# opensourus_voltceraptor_v1.net
KiCad netlist of a schematic drawn in EAGLE
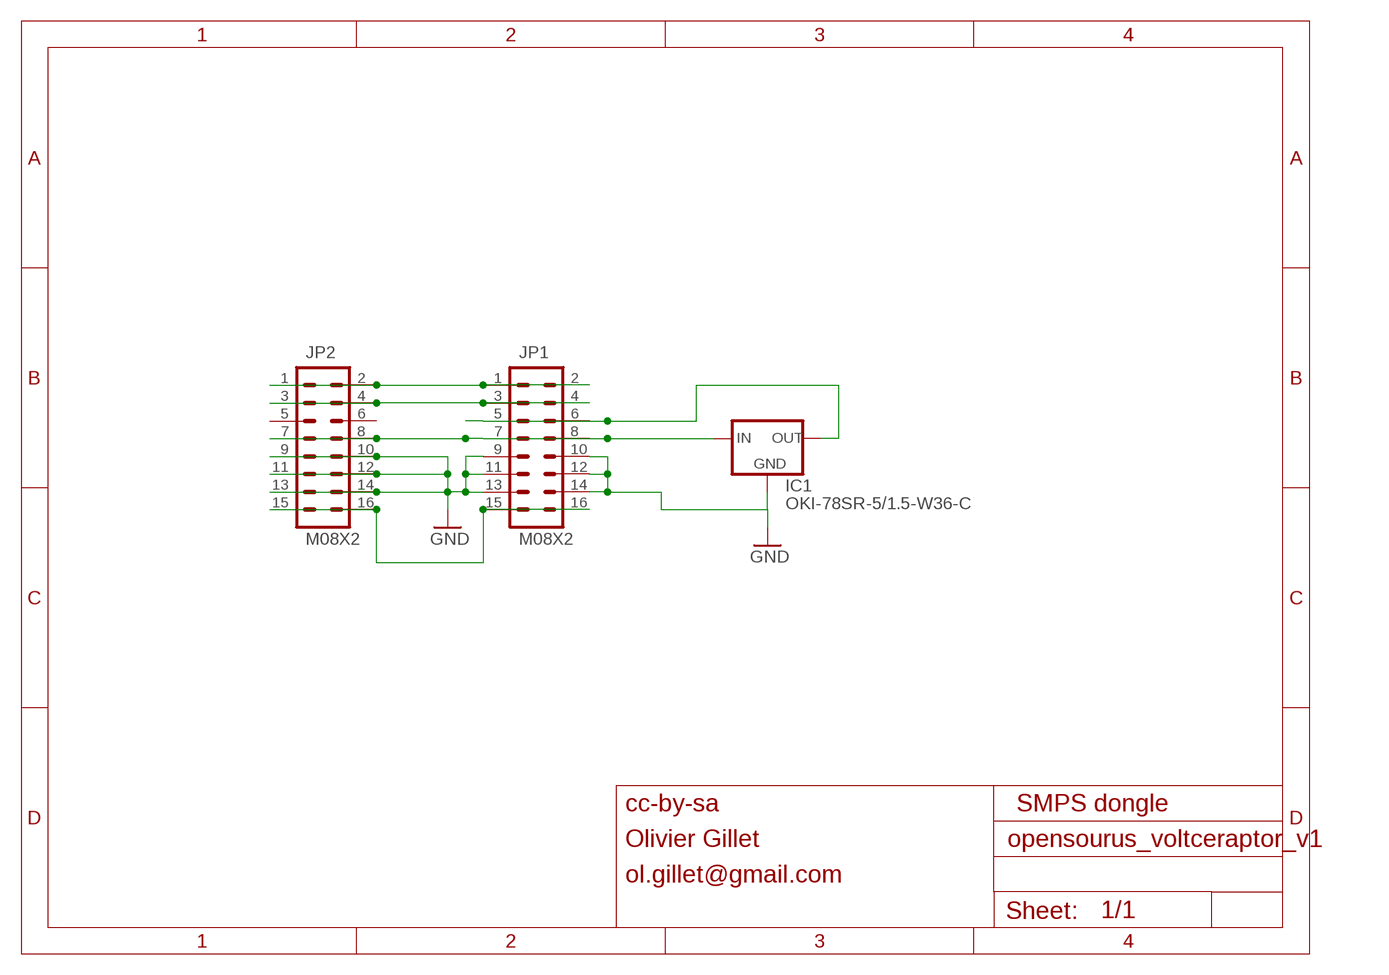
[diagram p0: schematic, sheet 1]

(export (version "E")
  (design (tool "Eeschema 10.0.6"))
  (components
    (comp (ref "IC1")
      (value "OKI-78SR-5/1.5-W36-C")
      (footprint "eagle-import:OKI78SR")
      (libsource (lib "eagle-import") (part "OKI-78SR"))
    )
    (comp (ref "JP1")
      (value "M08X2")
      (footprint "eagle-import:2X8")
      (libsource (lib "eagle-import") (part "M08X2"))
    )
    (comp (ref "JP2")
      (value "M08X2")
      (footprint "eagle-import:2X8")
      (libsource (lib "eagle-import") (part "M08X2"))
    )
  )
  (nets
    (net (code "1") (name "GND") (class "Default")
      (node (ref "IC1") (pin "2") (pinfunction "GND_2") (pintype "input"))
      (node (ref "JP1") (pin "10") (pinfunction "10_10") (pintype "passive"))
      (node (ref "JP1") (pin "11") (pinfunction "11_11") (pintype "passive"))
      (node (ref "JP1") (pin "12") (pinfunction "12_12") (pintype "passive"))
      (node (ref "JP1") (pin "13") (pinfunction "13_13") (pintype "passive"))
      (node (ref "JP1") (pin "14") (pinfunction "14_14") (pintype "passive"))
      (node (ref "JP1") (pin "9") (pinfunction "9_9") (pintype "passive"))
      (node (ref "JP2") (pin "10") (pinfunction "10_10") (pintype "passive"))
      (node (ref "JP2") (pin "11") (pinfunction "11_11") (pintype "passive"))
      (node (ref "JP2") (pin "12") (pinfunction "12_12") (pintype "passive"))
      (node (ref "JP2") (pin "13") (pinfunction "13_13") (pintype "passive"))
      (node (ref "JP2") (pin "14") (pinfunction "14_14") (pintype "passive"))
      (node (ref "JP2") (pin "9") (pinfunction "9_9") (pintype "passive"))
    )
    (net (code "2") (name "Net-(IC1-IN)") (class "Default")
      (node (ref "IC1") (pin "1") (pinfunction "IN_1") (pintype "input"))
      (node (ref "JP1") (pin "7") (pinfunction "7_7") (pintype "passive"))
      (node (ref "JP1") (pin "8") (pinfunction "8_8") (pintype "passive"))
      (node (ref "JP2") (pin "7") (pinfunction "7_7") (pintype "passive"))
      (node (ref "JP2") (pin "8") (pinfunction "8_8") (pintype "passive"))
    )
    (net (code "3") (name "Net-(IC1-OUT)") (class "Default")
      (node (ref "IC1") (pin "3") (pinfunction "OUT_3") (pintype "output"))
      (node (ref "JP1") (pin "5") (pinfunction "5_5") (pintype "passive"))
      (node (ref "JP1") (pin "6") (pinfunction "6_6") (pintype "passive"))
    )
    (net (code "4") (name "Net-(JP1-Pad1)") (class "Default")
      (node (ref "JP1") (pin "1") (pinfunction "1_1") (pintype "passive"))
      (node (ref "JP1") (pin "2") (pinfunction "2_2") (pintype "passive"))
      (node (ref "JP2") (pin "1") (pinfunction "1_1") (pintype "passive"))
      (node (ref "JP2") (pin "2") (pinfunction "2_2") (pintype "passive"))
    )
    (net (code "5") (name "Net-(JP1-Pad3)") (class "Default")
      (node (ref "JP1") (pin "3") (pinfunction "3_3") (pintype "passive"))
      (node (ref "JP1") (pin "4") (pinfunction "4_4") (pintype "passive"))
      (node (ref "JP2") (pin "3") (pinfunction "3_3") (pintype "passive"))
      (node (ref "JP2") (pin "4") (pinfunction "4_4") (pintype "passive"))
    )
    (net (code "6") (name "Net-(JP1-Pad15)") (class "Default")
      (node (ref "JP1") (pin "15") (pinfunction "15_15") (pintype "passive"))
      (node (ref "JP1") (pin "16") (pinfunction "16_16") (pintype "passive"))
      (node (ref "JP2") (pin "15") (pinfunction "15_15") (pintype "passive"))
      (node (ref "JP2") (pin "16") (pinfunction "16_16") (pintype "passive"))
    )
    (net (code "7") (name "unconnected-(JP2-Pad5)") (class "Default")
      (node (ref "JP2") (pin "5") (pinfunction "5_5") (pintype "passive"))
    )
    (net (code "8") (name "unconnected-(JP2-Pad6)") (class "Default")
      (node (ref "JP2") (pin "6") (pinfunction "6_6") (pintype "passive"))
    )
  )
)
